# EVK-NORA-W1_SCHEM_0005_Interface_Isolati.net
KiCad netlist of a schematic drawn in Altium Designer
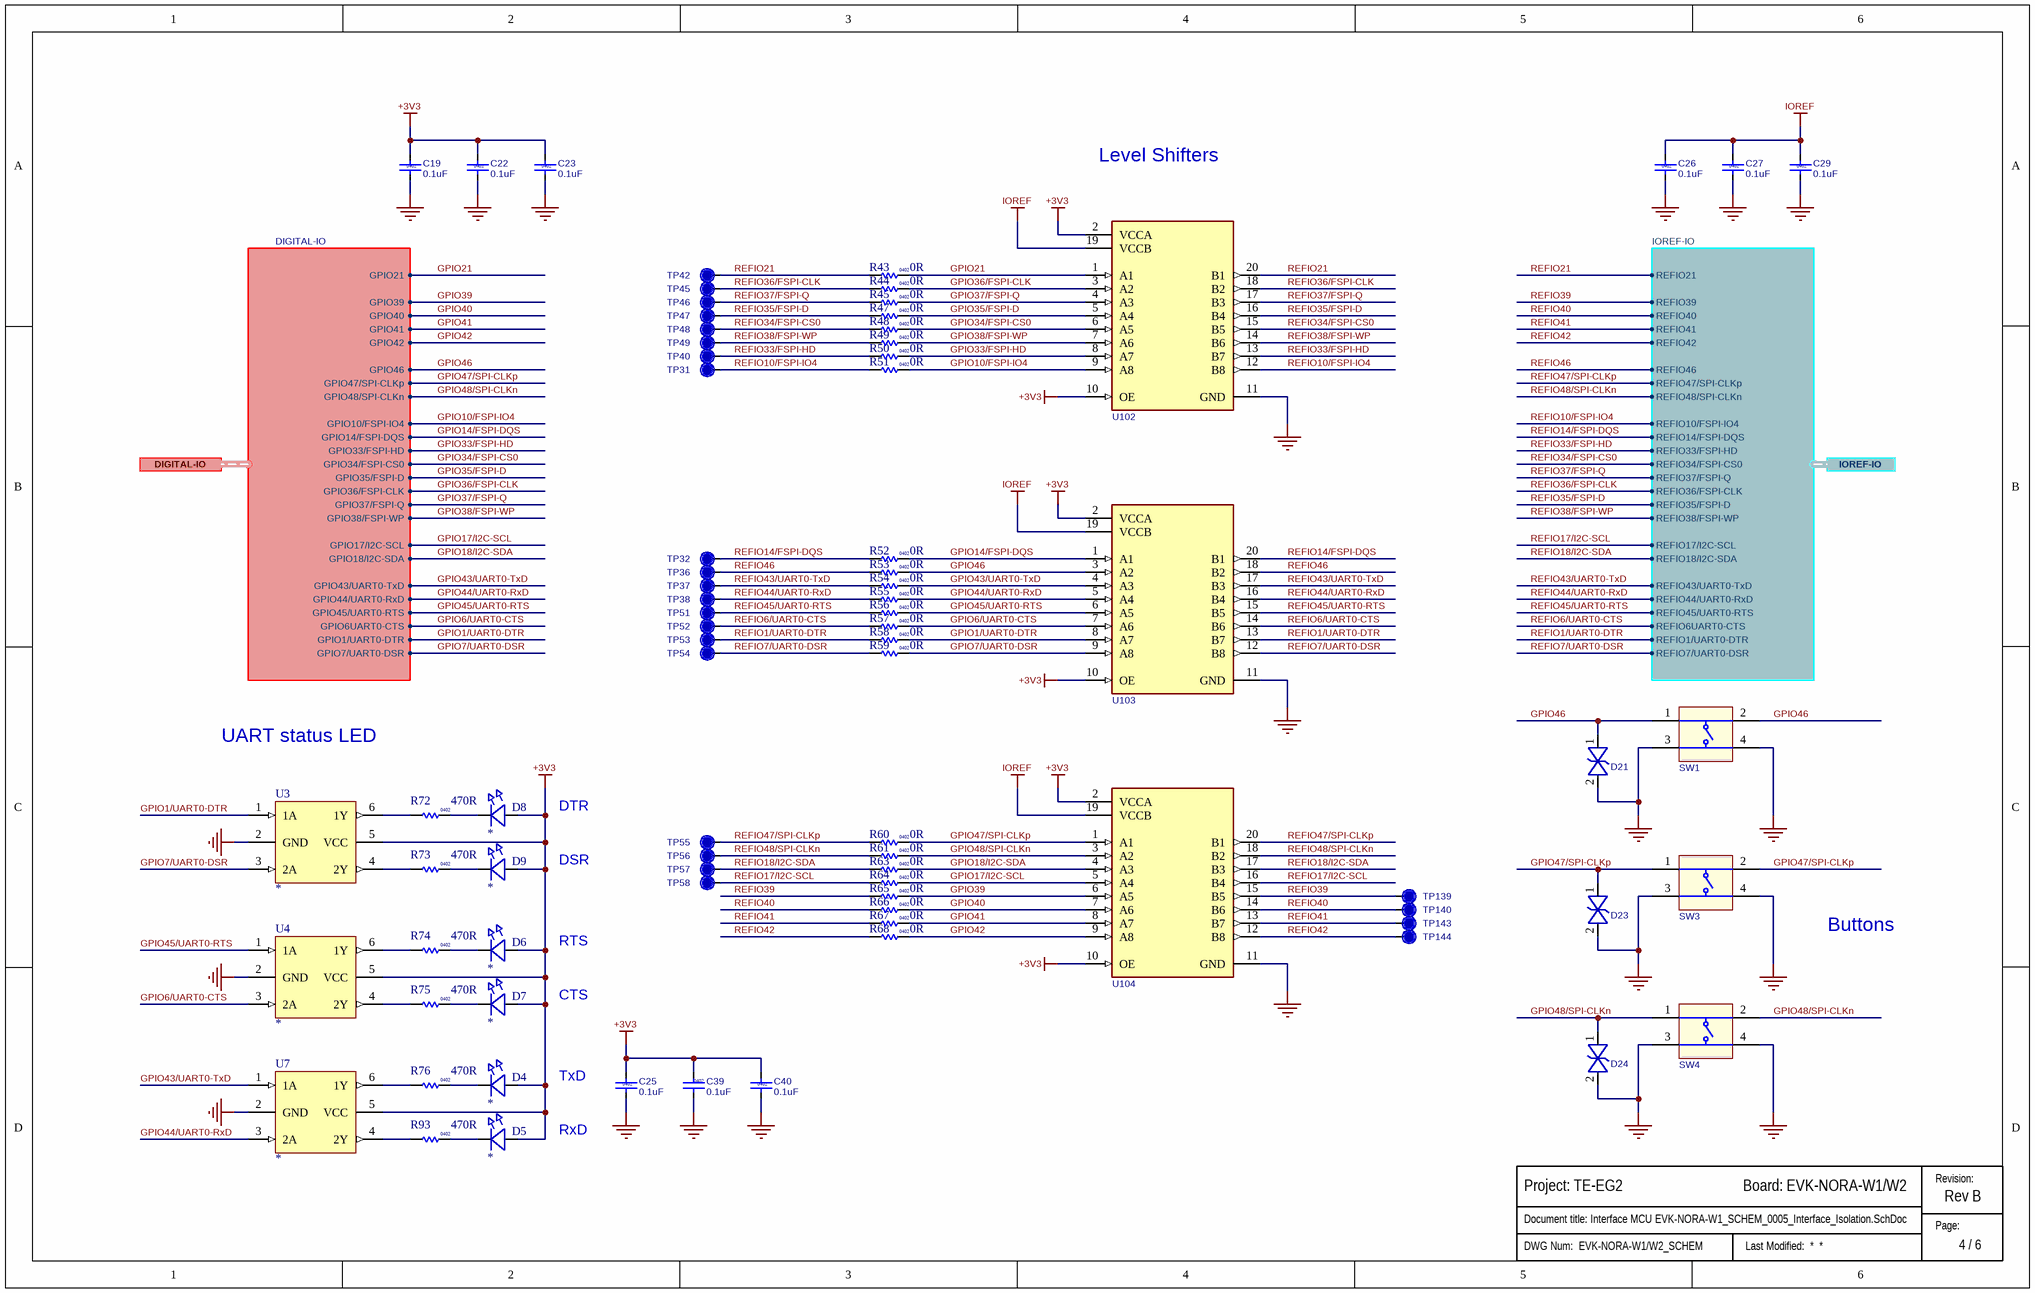
[diagram p0: EVK-NORA-W1_SCHEM_0005_Interface_Isolation.SchDoc]

(export (version "E")
  (design (tool "Eeschema 10.0.6"))
  (components
    (comp (ref "C19")
      (value "0.1uF")
      (footprint "Cap 0402 HD")
      (description "Cap, Ceramic 0.1uF 10V 10% X5R 0402")
      (fields
        (field (name "SIZE") "0402")
        (field (name "PART NUMBER") "120-00016")
        (field (name "MANUFACTURER") "Murata Electronics North America")
      )
      (libsource (lib "Arena_Parts_DB_Lib") (part "Cap Chip"))
    )
    (comp (ref "C22")
      (value "0.1uF")
      (footprint "Cap 0402 HD")
      (description "Cap, Ceramic 0.1uF 10V 10% X5R 0402")
      (fields
        (field (name "SIZE") "0402")
        (field (name "PART NUMBER") "120-00016")
        (field (name "MANUFACTURER") "Murata Electronics North America")
      )
      (libsource (lib "Arena_Parts_DB_Lib") (part "Cap Chip"))
    )
    (comp (ref "C23")
      (value "0.1uF")
      (footprint "Cap 0402 HD")
      (description "Cap, Ceramic 0.1uF 10V 10% X5R 0402")
      (fields
        (field (name "SIZE") "0402")
        (field (name "PART NUMBER") "120-00016")
        (field (name "MANUFACTURER") "Murata Electronics North America")
      )
      (libsource (lib "Arena_Parts_DB_Lib") (part "Cap Chip"))
    )
    (comp (ref "C25")
      (value "0.1uF")
      (footprint "Cap 0402 HD")
      (description "Cap, Ceramic 0.1uF 10V 10% X5R 0402")
      (fields
        (field (name "SIZE") "0402")
        (field (name "PART NUMBER") "120-00016")
        (field (name "MANUFACTURER") "Murata Electronics North America")
      )
      (libsource (lib "Arena_Parts_DB_Lib") (part "Cap Chip"))
    )
    (comp (ref "C26")
      (value "0.1uF")
      (footprint "Cap 0402 HD")
      (description "Cap, Ceramic 0.1uF 10V 10% X5R 0402")
      (fields
        (field (name "SIZE") "0402")
        (field (name "PART NUMBER") "120-00016")
        (field (name "MANUFACTURER") "Murata Electronics North America")
      )
      (libsource (lib "Arena_Parts_DB_Lib") (part "Cap Chip"))
    )
    (comp (ref "C27")
      (value "0.1uF")
      (footprint "Cap 0402 HD")
      (description "Cap, Ceramic 0.1uF 10V 10% X5R 0402")
      (fields
        (field (name "SIZE") "0402")
        (field (name "PART NUMBER") "120-00016")
        (field (name "MANUFACTURER") "Murata Electronics North America")
      )
      (libsource (lib "Arena_Parts_DB_Lib") (part "Cap Chip"))
    )
    (comp (ref "C29")
      (value "0.1uF")
      (footprint "Cap 0402 HD")
      (description "Cap, Ceramic 0.1uF 10V 10% X5R 0402")
      (fields
        (field (name "SIZE") "0402")
        (field (name "PART NUMBER") "120-00016")
        (field (name "MANUFACTURER") "Murata Electronics North America")
      )
      (libsource (lib "Arena_Parts_DB_Lib") (part "Cap Chip"))
    )
    (comp (ref "C39")
      (value "0.1uF")
      (footprint "Cap 0402 HD")
      (description "Cap, Ceramic 0.1uF 10V 10% X5R 0402")
      (fields
        (field (name "SIZE") "0402")
        (field (name "PART NUMBER") "120-00016")
        (field (name "MANUFACTURER") "Murata Electronics North America")
      )
      (libsource (lib "Arena_Parts_DB_Lib") (part "Cap Chip"))
    )
    (comp (ref "C40")
      (value "0.1uF")
      (footprint "Cap 0402 HD")
      (description "Cap, Ceramic 0.1uF 10V 10% X5R 0402")
      (fields
        (field (name "SIZE") "0402")
        (field (name "PART NUMBER") "120-00016")
        (field (name "MANUFACTURER") "Murata Electronics North America")
      )
      (libsource (lib "Arena_Parts_DB_Lib") (part "Cap Chip"))
    )
    (comp (ref "D4")
      (value "UBXH11-0000018")
      (footprint "LED-0603")
      (description "LED CHIP 0603 LOW CURRENT OSRAM 0.002A GREEN 2.2V 2mA")
      (fields
        (field (name "COLOR") "*")
        (field (name "MANUFACTURER") "Osram")
        (field (name "EDITOR") "johann.furrer")
        (field (name "RELEASED BY") "martin.grasse")
      )
      (libsource (lib "UBX_Parts_DB_Lib") (part "LED_BASE"))
    )
    (comp (ref "D5")
      (value "UBXH11-0000018")
      (footprint "LED-0603")
      (description "LED CHIP 0603 LOW CURRENT OSRAM 0.002A GREEN 2.2V 2mA")
      (fields
        (field (name "COLOR") "*")
        (field (name "MANUFACTURER") "Osram")
        (field (name "EDITOR") "johann.furrer")
        (field (name "RELEASED BY") "martin.grasse")
      )
      (libsource (lib "UBX_Parts_DB_Lib") (part "LED_BASE"))
    )
    (comp (ref "D6")
      (value "UBXH11-0000018")
      (footprint "LED-0603")
      (description "LED CHIP 0603 LOW CURRENT OSRAM 0.002A GREEN 2.2V 2mA")
      (fields
        (field (name "COLOR") "*")
        (field (name "MANUFACTURER") "Osram")
        (field (name "EDITOR") "johann.furrer")
        (field (name "RELEASED BY") "martin.grasse")
      )
      (libsource (lib "UBX_Parts_DB_Lib") (part "LED_BASE"))
    )
    (comp (ref "D7")
      (value "UBXH11-0000018")
      (footprint "LED-0603")
      (description "LED CHIP 0603 LOW CURRENT OSRAM 0.002A GREEN 2.2V 2mA")
      (fields
        (field (name "COLOR") "*")
        (field (name "MANUFACTURER") "Osram")
        (field (name "EDITOR") "johann.furrer")
        (field (name "RELEASED BY") "martin.grasse")
      )
      (libsource (lib "UBX_Parts_DB_Lib") (part "LED_BASE"))
    )
    (comp (ref "D8")
      (value "UBXH11-0000018")
      (footprint "LED-0603")
      (description "LED CHIP 0603 LOW CURRENT OSRAM 0.002A GREEN 2.2V 2mA")
      (fields
        (field (name "COLOR") "*")
        (field (name "MANUFACTURER") "Osram")
        (field (name "EDITOR") "johann.furrer")
        (field (name "RELEASED BY") "martin.grasse")
      )
      (libsource (lib "UBX_Parts_DB_Lib") (part "LED_BASE"))
    )
    (comp (ref "D9")
      (value "UBXH11-0000018")
      (footprint "LED-0603")
      (description "LED CHIP 0603 LOW CURRENT OSRAM 0.002A GREEN 2.2V 2mA")
      (fields
        (field (name "COLOR") "*")
        (field (name "MANUFACTURER") "Osram")
        (field (name "EDITOR") "johann.furrer")
        (field (name "RELEASED BY") "martin.grasse")
      )
      (libsource (lib "UBX_Parts_DB_Lib") (part "LED_BASE"))
    )
    (comp (ref "D21")
      (value "110-00019")
      (footprint "SOD-923")
      (description "ESD9B3.3ST5G")
      (fields (field (name "MANUFACTURER") "ON Semiconductor") (field (name "VOLTAGE") "3.3V"))
      (libsource (lib "Arena_Parts_DB_Lib") (part "Diode_TVS"))
    )
    (comp (ref "D23")
      (value "110-00019")
      (footprint "SOD-923")
      (description "ESD9B3.3ST5G")
      (fields (field (name "MANUFACTURER") "ON Semiconductor") (field (name "VOLTAGE") "3.3V"))
      (libsource (lib "Arena_Parts_DB_Lib") (part "Diode_TVS"))
    )
    (comp (ref "D24")
      (value "110-00019")
      (footprint "SOD-923")
      (description "ESD9B3.3ST5G")
      (fields (field (name "MANUFACTURER") "ON Semiconductor") (field (name "VOLTAGE") "3.3V"))
      (libsource (lib "Arena_Parts_DB_Lib") (part "Diode_TVS"))
    )
    (comp (ref "R43")
      (value "0R")
      (footprint "RES 0402 HD")
      (description "RES THICK FILM CHIP 0402 0R 0 100mW")
      (fields
        (field (name "SIZE") "0402")
        (field (name "PART NUMBER") "UBXH18-0003002")
        (field (name "TOLERANCE") "0")
        (field (name "EDITOR") "charlotte.biber")
        (field (name "RELEASED BY") "peter.mueller")
      )
      (libsource (lib "UBX_Parts_DB_Lib") (part "Res sm"))
    )
    (comp (ref "R44")
      (value "0R")
      (footprint "RES 0402 HD")
      (description "RES THICK FILM CHIP 0402 0R 0 100mW")
      (fields
        (field (name "SIZE") "0402")
        (field (name "PART NUMBER") "UBXH18-0003002")
        (field (name "TOLERANCE") "0")
        (field (name "EDITOR") "charlotte.biber")
        (field (name "RELEASED BY") "peter.mueller")
      )
      (libsource (lib "UBX_Parts_DB_Lib") (part "Res sm"))
    )
    (comp (ref "R45")
      (value "0R")
      (footprint "RES 0402 HD")
      (description "RES THICK FILM CHIP 0402 0R 0 100mW")
      (fields
        (field (name "SIZE") "0402")
        (field (name "PART NUMBER") "UBXH18-0003002")
        (field (name "TOLERANCE") "0")
        (field (name "EDITOR") "charlotte.biber")
        (field (name "RELEASED BY") "peter.mueller")
      )
      (libsource (lib "UBX_Parts_DB_Lib") (part "Res sm"))
    )
    (comp (ref "R47")
      (value "0R")
      (footprint "RES 0402 HD")
      (description "RES THICK FILM CHIP 0402 0R 0 100mW")
      (fields
        (field (name "SIZE") "0402")
        (field (name "PART NUMBER") "UBXH18-0003002")
        (field (name "TOLERANCE") "0")
        (field (name "EDITOR") "charlotte.biber")
        (field (name "RELEASED BY") "peter.mueller")
      )
      (libsource (lib "UBX_Parts_DB_Lib") (part "Res sm"))
    )
    (comp (ref "R48")
      (value "0R")
      (footprint "RES 0402 HD")
      (description "RES THICK FILM CHIP 0402 0R 0 100mW")
      (fields
        (field (name "SIZE") "0402")
        (field (name "PART NUMBER") "UBXH18-0003002")
        (field (name "TOLERANCE") "0")
        (field (name "EDITOR") "charlotte.biber")
        (field (name "RELEASED BY") "peter.mueller")
      )
      (libsource (lib "UBX_Parts_DB_Lib") (part "Res sm"))
    )
    (comp (ref "R49")
      (value "0R")
      (footprint "RES 0402 HD")
      (description "RES THICK FILM CHIP 0402 0R 0 100mW")
      (fields
        (field (name "SIZE") "0402")
        (field (name "PART NUMBER") "UBXH18-0003002")
        (field (name "TOLERANCE") "0")
        (field (name "EDITOR") "charlotte.biber")
        (field (name "RELEASED BY") "peter.mueller")
      )
      (libsource (lib "UBX_Parts_DB_Lib") (part "Res sm"))
    )
    (comp (ref "R50")
      (value "0R")
      (footprint "RES 0402 HD")
      (description "RES THICK FILM CHIP 0402 0R 0 100mW")
      (fields
        (field (name "SIZE") "0402")
        (field (name "PART NUMBER") "UBXH18-0003002")
        (field (name "TOLERANCE") "0")
        (field (name "EDITOR") "charlotte.biber")
        (field (name "RELEASED BY") "peter.mueller")
      )
      (libsource (lib "UBX_Parts_DB_Lib") (part "Res sm"))
    )
    (comp (ref "R51")
      (value "0R")
      (footprint "RES 0402 HD")
      (description "RES THICK FILM CHIP 0402 0R 0 100mW")
      (fields
        (field (name "SIZE") "0402")
        (field (name "PART NUMBER") "UBXH18-0003002")
        (field (name "TOLERANCE") "0")
        (field (name "EDITOR") "charlotte.biber")
        (field (name "RELEASED BY") "peter.mueller")
      )
      (libsource (lib "UBX_Parts_DB_Lib") (part "Res sm"))
    )
    (comp (ref "R52")
      (value "0R")
      (footprint "RES 0402 HD")
      (description "RES THICK FILM CHIP 0402 0R 0 100mW")
      (fields
        (field (name "SIZE") "0402")
        (field (name "PART NUMBER") "UBXH18-0003002")
        (field (name "TOLERANCE") "0")
        (field (name "EDITOR") "charlotte.biber")
        (field (name "RELEASED BY") "peter.mueller")
      )
      (libsource (lib "UBX_Parts_DB_Lib") (part "Res sm"))
    )
    (comp (ref "R53")
      (value "0R")
      (footprint "RES 0402 HD")
      (description "RES THICK FILM CHIP 0402 0R 0 100mW")
      (fields
        (field (name "SIZE") "0402")
        (field (name "PART NUMBER") "UBXH18-0003002")
        (field (name "TOLERANCE") "0")
        (field (name "EDITOR") "charlotte.biber")
        (field (name "RELEASED BY") "peter.mueller")
      )
      (libsource (lib "UBX_Parts_DB_Lib") (part "Res sm"))
    )
    (comp (ref "R54")
      (value "0R")
      (footprint "RES 0402 HD")
      (description "RES THICK FILM CHIP 0402 0R 0 100mW")
      (fields
        (field (name "SIZE") "0402")
        (field (name "PART NUMBER") "UBXH18-0003002")
        (field (name "TOLERANCE") "0")
        (field (name "EDITOR") "charlotte.biber")
        (field (name "RELEASED BY") "peter.mueller")
      )
      (libsource (lib "UBX_Parts_DB_Lib") (part "Res sm"))
    )
    (comp (ref "R55")
      (value "0R")
      (footprint "RES 0402 HD")
      (description "RES THICK FILM CHIP 0402 0R 0 100mW")
      (fields
        (field (name "SIZE") "0402")
        (field (name "PART NUMBER") "UBXH18-0003002")
        (field (name "TOLERANCE") "0")
        (field (name "EDITOR") "charlotte.biber")
        (field (name "RELEASED BY") "peter.mueller")
      )
      (libsource (lib "UBX_Parts_DB_Lib") (part "Res sm"))
    )
    (comp (ref "R56")
      (value "0R")
      (footprint "RES 0402 HD")
      (description "RES THICK FILM CHIP 0402 0R 0 100mW")
      (fields
        (field (name "SIZE") "0402")
        (field (name "PART NUMBER") "UBXH18-0003002")
        (field (name "TOLERANCE") "0")
        (field (name "EDITOR") "charlotte.biber")
        (field (name "RELEASED BY") "peter.mueller")
      )
      (libsource (lib "UBX_Parts_DB_Lib") (part "Res sm"))
    )
    (comp (ref "R57")
      (value "0R")
      (footprint "RES 0402 HD")
      (description "RES THICK FILM CHIP 0402 0R 0 100mW")
      (fields
        (field (name "SIZE") "0402")
        (field (name "PART NUMBER") "UBXH18-0003002")
        (field (name "TOLERANCE") "0")
        (field (name "EDITOR") "charlotte.biber")
        (field (name "RELEASED BY") "peter.mueller")
      )
      (libsource (lib "UBX_Parts_DB_Lib") (part "Res sm"))
    )
    (comp (ref "R58")
      (value "0R")
      (footprint "RES 0402 HD")
      (description "RES THICK FILM CHIP 0402 0R 0 100mW")
      (fields
        (field (name "SIZE") "0402")
        (field (name "PART NUMBER") "UBXH18-0003002")
        (field (name "TOLERANCE") "0")
        (field (name "EDITOR") "charlotte.biber")
        (field (name "RELEASED BY") "peter.mueller")
      )
      (libsource (lib "UBX_Parts_DB_Lib") (part "Res sm"))
    )
    (comp (ref "R59")
      (value "0R")
      (footprint "RES 0402 HD")
      (description "RES THICK FILM CHIP 0402 0R 0 100mW")
      (fields
        (field (name "SIZE") "0402")
        (field (name "PART NUMBER") "UBXH18-0003002")
        (field (name "TOLERANCE") "0")
        (field (name "EDITOR") "charlotte.biber")
        (field (name "RELEASED BY") "peter.mueller")
      )
      (libsource (lib "UBX_Parts_DB_Lib") (part "Res sm"))
    )
    (comp (ref "R60")
      (value "0R")
      (footprint "RES 0402 HD")
      (description "RES THICK FILM CHIP 0402 0R 0 100mW")
      (fields
        (field (name "SIZE") "0402")
        (field (name "PART NUMBER") "UBXH18-0003002")
        (field (name "TOLERANCE") "0")
        (field (name "EDITOR") "charlotte.biber")
        (field (name "RELEASED BY") "peter.mueller")
      )
      (libsource (lib "UBX_Parts_DB_Lib") (part "Res sm"))
    )
    (comp (ref "R61")
      (value "0R")
      (footprint "RES 0402 HD")
      (description "RES THICK FILM CHIP 0402 0R 0 100mW")
      (fields
        (field (name "SIZE") "0402")
        (field (name "PART NUMBER") "UBXH18-0003002")
        (field (name "TOLERANCE") "0")
        (field (name "EDITOR") "charlotte.biber")
        (field (name "RELEASED BY") "peter.mueller")
      )
      (libsource (lib "UBX_Parts_DB_Lib") (part "Res sm"))
    )
    (comp (ref "R63")
      (value "0R")
      (footprint "RES 0402 HD")
      (description "RES THICK FILM CHIP 0402 0R 0 100mW")
      (fields
        (field (name "SIZE") "0402")
        (field (name "PART NUMBER") "UBXH18-0003002")
        (field (name "TOLERANCE") "0")
        (field (name "EDITOR") "charlotte.biber")
        (field (name "RELEASED BY") "peter.mueller")
      )
      (libsource (lib "UBX_Parts_DB_Lib") (part "Res sm"))
    )
    (comp (ref "R64")
      (value "0R")
      (footprint "RES 0402 HD")
      (description "RES THICK FILM CHIP 0402 0R 0 100mW")
      (fields
        (field (name "SIZE") "0402")
        (field (name "PART NUMBER") "UBXH18-0003002")
        (field (name "TOLERANCE") "0")
        (field (name "EDITOR") "charlotte.biber")
        (field (name "RELEASED BY") "peter.mueller")
      )
      (libsource (lib "UBX_Parts_DB_Lib") (part "Res sm"))
    )
    (comp (ref "R65")
      (value "0R")
      (footprint "RES 0402 HD")
      (description "RES THICK FILM CHIP 0402 0R 0 100mW")
      (fields
        (field (name "SIZE") "0402")
        (field (name "PART NUMBER") "UBXH18-0003002")
        (field (name "TOLERANCE") "0")
        (field (name "EDITOR") "charlotte.biber")
        (field (name "RELEASED BY") "peter.mueller")
      )
      (libsource (lib "UBX_Parts_DB_Lib") (part "Res sm"))
    )
    (comp (ref "R66")
      (value "0R")
      (footprint "RES 0402 HD")
      (description "RES THICK FILM CHIP 0402 0R 0 100mW")
      (fields
        (field (name "SIZE") "0402")
        (field (name "PART NUMBER") "UBXH18-0003002")
        (field (name "TOLERANCE") "0")
        (field (name "EDITOR") "charlotte.biber")
        (field (name "RELEASED BY") "peter.mueller")
      )
      (libsource (lib "UBX_Parts_DB_Lib") (part "Res sm"))
    )
    (comp (ref "R67")
      (value "0R")
      (footprint "RES 0402 HD")
      (description "RES THICK FILM CHIP 0402 0R 0 100mW")
      (fields
        (field (name "SIZE") "0402")
        (field (name "PART NUMBER") "UBXH18-0003002")
        (field (name "TOLERANCE") "0")
        (field (name "EDITOR") "charlotte.biber")
        (field (name "RELEASED BY") "peter.mueller")
      )
      (libsource (lib "UBX_Parts_DB_Lib") (part "Res sm"))
    )
    (comp (ref "R68")
      (value "0R")
      (footprint "RES 0402 HD")
      (description "RES THICK FILM CHIP 0402 0R 0 100mW")
      (fields
        (field (name "SIZE") "0402")
        (field (name "PART NUMBER") "UBXH18-0003002")
        (field (name "TOLERANCE") "0")
        (field (name "EDITOR") "charlotte.biber")
        (field (name "RELEASED BY") "peter.mueller")
      )
      (libsource (lib "UBX_Parts_DB_Lib") (part "Res sm"))
    )
    (comp (ref "R72")
      (value "470R")
      (footprint "RES 0402 HD")
      (description "RES THICK FILM CHIP 0402 470R 5% 100mW")
      (fields
        (field (name "SIZE") "0402")
        (field (name "PART NUMBER") "UBXH18-0008041")
        (field (name "TOLERANCE") "5%")
        (field (name "EDITOR") "roland.rust")
        (field (name "RELEASED BY") "roland.rust")
      )
      (libsource (lib "UBX_Parts_DB_Lib") (part "Res sm"))
    )
    (comp (ref "R73")
      (value "470R")
      (footprint "RES 0402 HD")
      (description "RES THICK FILM CHIP 0402 470R 5% 100mW")
      (fields
        (field (name "SIZE") "0402")
        (field (name "PART NUMBER") "UBXH18-0008041")
        (field (name "TOLERANCE") "5%")
        (field (name "EDITOR") "roland.rust")
        (field (name "RELEASED BY") "roland.rust")
      )
      (libsource (lib "UBX_Parts_DB_Lib") (part "Res sm"))
    )
    (comp (ref "R74")
      (value "470R")
      (footprint "RES 0402 HD")
      (description "RES THICK FILM CHIP 0402 470R 5% 100mW")
      (fields
        (field (name "SIZE") "0402")
        (field (name "PART NUMBER") "UBXH18-0008041")
        (field (name "TOLERANCE") "5%")
        (field (name "EDITOR") "roland.rust")
        (field (name "RELEASED BY") "roland.rust")
      )
      (libsource (lib "UBX_Parts_DB_Lib") (part "Res sm"))
    )
    (comp (ref "R75")
      (value "470R")
      (footprint "RES 0402 HD")
      (description "RES THICK FILM CHIP 0402 470R 5% 100mW")
      (fields
        (field (name "SIZE") "0402")
        (field (name "PART NUMBER") "UBXH18-0008041")
        (field (name "TOLERANCE") "5%")
        (field (name "EDITOR") "roland.rust")
        (field (name "RELEASED BY") "roland.rust")
      )
      (libsource (lib "UBX_Parts_DB_Lib") (part "Res sm"))
    )
    (comp (ref "R76")
      (value "470R")
      (footprint "RES 0402 HD")
      (description "RES THICK FILM CHIP 0402 470R 5% 100mW")
      (fields
        (field (name "SIZE") "0402")
        (field (name "PART NUMBER") "UBXH18-0008041")
        (field (name "TOLERANCE") "5%")
        (field (name "EDITOR") "roland.rust")
        (field (name "RELEASED BY") "roland.rust")
      )
      (libsource (lib "UBX_Parts_DB_Lib") (part "Res sm"))
    )
    (comp (ref "R93")
      (value "470R")
      (footprint "RES 0402 HD")
      (description "RES THICK FILM CHIP 0402 470R 5% 100mW")
      (fields
        (field (name "SIZE") "0402")
        (field (name "PART NUMBER") "UBXH18-0008041")
        (field (name "TOLERANCE") "5%")
        (field (name "EDITOR") "roland.rust")
        (field (name "RELEASED BY") "roland.rust")
      )
      (libsource (lib "UBX_Parts_DB_Lib") (part "Res sm"))
    )
    (comp (ref "SW1")
      (value "135-00002")
      (footprint "SW_TACT_SMT_6mm")
      (description "Tactile Switch, SPST-NO, SMT, Actuation force = 160g, 6mm x 6mm")
      (fields (field (name "MANUFACTURER") "C&K Components") (field (name "VOLTAGE") "12VDC"))
      (libsource (lib "Arena_Parts_DB_Lib") (part "SW_TACT_SPST_4Pin"))
    )
    (comp (ref "SW3")
      (value "135-00002")
      (footprint "SW_TACT_SMT_6mm")
      (description "Tactile Switch, SPST-NO, SMT, Actuation force = 160g, 6mm x 6mm")
      (fields (field (name "MANUFACTURER") "C&K Components") (field (name "VOLTAGE") "12VDC"))
      (libsource (lib "Arena_Parts_DB_Lib") (part "SW_TACT_SPST_4Pin"))
    )
    (comp (ref "SW4")
      (value "135-00002")
      (footprint "SW_TACT_SMT_6mm")
      (description "Tactile Switch, SPST-NO, SMT, Actuation force = 160g, 6mm x 6mm")
      (fields (field (name "MANUFACTURER") "C&K Components") (field (name "VOLTAGE") "12VDC"))
      (libsource (lib "Arena_Parts_DB_Lib") (part "SW_TACT_SPST_4Pin"))
    )
    (comp (ref "TP31")
      (value "TP")
      (footprint "TP10R")
      (description "Testpoint, Round 1.0mm Dia")
      (fields
        (field (name "PART NUMBER") "TP10R")
        (field (name "ADDED BY") "Jeremy D")
        (field (name "CHECKED BY") "Paul B")
      )
      (libsource (lib "LEGACY_Rigado_AltiumLib") (part "TP_R"))
    )
    (comp (ref "TP32")
      (value "TP")
      (footprint "TP10R")
      (description "Testpoint, Round 1.0mm Dia")
      (fields
        (field (name "PART NUMBER") "TP10R")
        (field (name "ADDED BY") "Jeremy D")
        (field (name "CHECKED BY") "Paul B")
      )
      (libsource (lib "LEGACY_Rigado_AltiumLib") (part "TP_R"))
    )
    (comp (ref "TP36")
      (value "TP")
      (footprint "TP10R")
      (description "Testpoint, Round 1.0mm Dia")
      (fields
        (field (name "PART NUMBER") "TP10R")
        (field (name "ADDED BY") "Jeremy D")
        (field (name "CHECKED BY") "Paul B")
      )
      (libsource (lib "LEGACY_Rigado_AltiumLib") (part "TP_R"))
    )
    (comp (ref "TP37")
      (value "TP")
      (footprint "TP10R")
      (description "Testpoint, Round 1.0mm Dia")
      (fields
        (field (name "PART NUMBER") "TP10R")
        (field (name "ADDED BY") "Jeremy D")
        (field (name "CHECKED BY") "Paul B")
      )
      (libsource (lib "LEGACY_Rigado_AltiumLib") (part "TP_R"))
    )
    (comp (ref "TP38")
      (value "TP")
      (footprint "TP10R")
      (description "Testpoint, Round 1.0mm Dia")
      (fields
        (field (name "PART NUMBER") "TP10R")
        (field (name "ADDED BY") "Jeremy D")
        (field (name "CHECKED BY") "Paul B")
      )
      (libsource (lib "LEGACY_Rigado_AltiumLib") (part "TP_R"))
    )
    (comp (ref "TP40")
      (value "TP")
      (footprint "TP10R")
      (description "Testpoint, Round 1.0mm Dia")
      (fields
        (field (name "PART NUMBER") "TP10R")
        (field (name "ADDED BY") "Jeremy D")
        (field (name "CHECKED BY") "Paul B")
      )
      (libsource (lib "LEGACY_Rigado_AltiumLib") (part "TP_R"))
    )
    (comp (ref "TP42")
      (value "TP")
      (footprint "TP10R")
      (description "Testpoint, Round 1.0mm Dia")
      (fields
        (field (name "PART NUMBER") "TP10R")
        (field (name "ADDED BY") "Jeremy D")
        (field (name "CHECKED BY") "Paul B")
      )
      (libsource (lib "LEGACY_Rigado_AltiumLib") (part "TP_R"))
    )
    (comp (ref "TP45")
      (value "TP")
      (footprint "TP10R")
      (description "Testpoint, Round 1.0mm Dia")
      (fields
        (field (name "PART NUMBER") "TP10R")
        (field (name "ADDED BY") "Jeremy D")
        (field (name "CHECKED BY") "Paul B")
      )
      (libsource (lib "LEGACY_Rigado_AltiumLib") (part "TP_R"))
    )
    (comp (ref "TP46")
      (value "TP")
      (footprint "TP10R")
      (description "Testpoint, Round 1.0mm Dia")
      (fields
        (field (name "PART NUMBER") "TP10R")
        (field (name "ADDED BY") "Jeremy D")
        (field (name "CHECKED BY") "Paul B")
      )
      (libsource (lib "LEGACY_Rigado_AltiumLib") (part "TP_R"))
    )
    (comp (ref "TP47")
      (value "TP")
      (footprint "TP10R")
      (description "Testpoint, Round 1.0mm Dia")
      (fields
        (field (name "PART NUMBER") "TP10R")
        (field (name "ADDED BY") "Jeremy D")
        (field (name "CHECKED BY") "Paul B")
      )
      (libsource (lib "LEGACY_Rigado_AltiumLib") (part "TP_R"))
    )
    (comp (ref "TP48")
      (value "TP")
      (footprint "TP10R")
      (description "Testpoint, Round 1.0mm Dia")
      (fields
        (field (name "PART NUMBER") "TP10R")
        (field (name "ADDED BY") "Jeremy D")
        (field (name "CHECKED BY") "Paul B")
      )
      (libsource (lib "LEGACY_Rigado_AltiumLib") (part "TP_R"))
    )
    (comp (ref "TP49")
      (value "TP")
      (footprint "TP10R")
      (description "Testpoint, Round 1.0mm Dia")
      (fields
        (field (name "PART NUMBER") "TP10R")
        (field (name "ADDED BY") "Jeremy D")
        (field (name "CHECKED BY") "Paul B")
      )
      (libsource (lib "LEGACY_Rigado_AltiumLib") (part "TP_R"))
    )
    (comp (ref "TP51")
      (value "TP")
      (footprint "TP10R")
      (description "Testpoint, Round 1.0mm Dia")
      (fields
        (field (name "PART NUMBER") "TP10R")
        (field (name "ADDED BY") "Jeremy D")
        (field (name "CHECKED BY") "Paul B")
      )
      (libsource (lib "LEGACY_Rigado_AltiumLib") (part "TP_R"))
    )
    (comp (ref "TP52")
      (value "TP")
      (footprint "TP10R")
      (description "Testpoint, Round 1.0mm Dia")
      (fields
        (field (name "PART NUMBER") "TP10R")
        (field (name "ADDED BY") "Jeremy D")
        (field (name "CHECKED BY") "Paul B")
      )
      (libsource (lib "LEGACY_Rigado_AltiumLib") (part "TP_R"))
    )
    (comp (ref "TP53")
      (value "TP")
      (footprint "TP10R")
      (description "Testpoint, Round 1.0mm Dia")
      (fields
        (field (name "PART NUMBER") "TP10R")
        (field (name "ADDED BY") "Jeremy D")
        (field (name "CHECKED BY") "Paul B")
      )
      (libsource (lib "LEGACY_Rigado_AltiumLib") (part "TP_R"))
    )
    (comp (ref "TP54")
      (value "TP")
      (footprint "TP10R")
      (description "Testpoint, Round 1.0mm Dia")
      (fields
        (field (name "PART NUMBER") "TP10R")
        (field (name "ADDED BY") "Jeremy D")
        (field (name "CHECKED BY") "Paul B")
      )
      (libsource (lib "LEGACY_Rigado_AltiumLib") (part "TP_R"))
    )
    (comp (ref "TP55")
      (value "TP")
      (footprint "TP10R")
      (description "Testpoint, Round 1.0mm Dia")
      (fields
        (field (name "PART NUMBER") "TP10R")
        (field (name "ADDED BY") "Jeremy D")
        (field (name "CHECKED BY") "Paul B")
      )
      (libsource (lib "LEGACY_Rigado_AltiumLib") (part "TP_R"))
    )
    (comp (ref "TP56")
      (value "TP")
      (footprint "TP10R")
      (description "Testpoint, Round 1.0mm Dia")
      (fields
        (field (name "PART NUMBER") "TP10R")
        (field (name "ADDED BY") "Jeremy D")
        (field (name "CHECKED BY") "Paul B")
      )
      (libsource (lib "LEGACY_Rigado_AltiumLib") (part "TP_R"))
    )
    (comp (ref "TP57")
      (value "TP")
      (footprint "TP10R")
      (description "Testpoint, Round 1.0mm Dia")
      (fields
        (field (name "PART NUMBER") "TP10R")
        (field (name "ADDED BY") "Jeremy D")
        (field (name "CHECKED BY") "Paul B")
      )
      (libsource (lib "LEGACY_Rigado_AltiumLib") (part "TP_R"))
    )
    (comp (ref "TP58")
      (value "TP")
      (footprint "TP10R")
      (description "Testpoint, Round 1.0mm Dia")
      (fields
        (field (name "PART NUMBER") "TP10R")
        (field (name "ADDED BY") "Jeremy D")
        (field (name "CHECKED BY") "Paul B")
      )
      (libsource (lib "LEGACY_Rigado_AltiumLib") (part "TP_R"))
    )
    (comp (ref "TP139")
      (value "TP")
      (footprint "TP10R")
      (description "Testpoint, Round 1.0mm Dia")
      (fields
        (field (name "PART NUMBER") "TP10R")
        (field (name "ADDED BY") "Jeremy D")
        (field (name "CHECKED BY") "Paul B")
      )
      (libsource (lib "LEGACY_Rigado_AltiumLib") (part "TP_R"))
    )
    (comp (ref "TP140")
      (value "TP")
      (footprint "TP10R")
      (description "Testpoint, Round 1.0mm Dia")
      (fields
        (field (name "PART NUMBER") "TP10R")
        (field (name "ADDED BY") "Jeremy D")
        (field (name "CHECKED BY") "Paul B")
      )
      (libsource (lib "LEGACY_Rigado_AltiumLib") (part "TP_R"))
    )
    (comp (ref "TP143")
      (value "TP")
      (footprint "TP10R")
      (description "Testpoint, Round 1.0mm Dia")
      (fields
        (field (name "PART NUMBER") "TP10R")
        (field (name "ADDED BY") "Jeremy D")
        (field (name "CHECKED BY") "Paul B")
      )
      (libsource (lib "LEGACY_Rigado_AltiumLib") (part "TP_R"))
    )
    (comp (ref "TP144")
      (value "TP")
      (footprint "TP10R")
      (description "Testpoint, Round 1.0mm Dia")
      (fields
        (field (name "PART NUMBER") "TP10R")
        (field (name "ADDED BY") "Jeremy D")
        (field (name "CHECKED BY") "Paul B")
      )
      (libsource (lib "LEGACY_Rigado_AltiumLib") (part "TP_R"))
    )
    (comp (ref "U3")
      (value "225-00022")
      (footprint "SC70-6")
      (description "Buffer, Non-Inverting 2 Element 1 Bit per Element Push-Pull Output SC-70-6")
      (fields (field (name "MANUFACTURER P/N") "*") (field (name "VOLTAGE") "5.5V"))
      (libsource (lib "Arena_Parts_DB_Lib") (part "Buffer_2bit"))
    )
    (comp (ref "U4")
      (value "225-00022")
      (footprint "SC70-6")
      (description "Buffer, Non-Inverting 2 Element 1 Bit per Element Push-Pull Output SC-70-6")
      (fields (field (name "MANUFACTURER P/N") "*") (field (name "VOLTAGE") "5.5V"))
      (libsource (lib "Arena_Parts_DB_Lib") (part "Buffer_2bit"))
    )
    (comp (ref "U7")
      (value "225-00022")
      (footprint "SC70-6")
      (description "Buffer, Non-Inverting 2 Element 1 Bit per Element Push-Pull Output SC-70-6")
      (fields (field (name "MANUFACTURER P/N") "*") (field (name "VOLTAGE") "5.5V"))
      (libsource (lib "Arena_Parts_DB_Lib") (part "Buffer_2bit"))
    )
    (comp (ref "U102")
      (value "TXS0108EPWR")
      (footprint "TSSOP-20Pin-6.5x6.4")
      (description "TXS0108 8-BIT BIDIRECTIONAL VOLTAGE-LEVEL TRANSLATOR")
      (fields
        (field (name "PART NUMBER") "UBXH10-0000036")
        (field (name "MANUFACTURER") "Texas Instruments")
        (field (name "EDITOR") "roland.rust")
        (field (name "RELEASED BY") "adam.johansson")
      )
      (libsource (lib "UBX_Parts_DB_Lib") (part "TXS0108EPWR"))
    )
    (comp (ref "U103")
      (value "TXS0108EPWR")
      (footprint "TSSOP-20Pin-6.5x6.4")
      (description "TXS0108 8-BIT BIDIRECTIONAL VOLTAGE-LEVEL TRANSLATOR")
      (fields
        (field (name "PART NUMBER") "UBXH10-0000036")
        (field (name "MANUFACTURER") "Texas Instruments")
        (field (name "EDITOR") "roland.rust")
        (field (name "RELEASED BY") "adam.johansson")
      )
      (libsource (lib "UBX_Parts_DB_Lib") (part "TXS0108EPWR"))
    )
    (comp (ref "U104")
      (value "TXS0108EPWR")
      (footprint "TSSOP-20Pin-6.5x6.4")
      (description "TXS0108 8-BIT BIDIRECTIONAL VOLTAGE-LEVEL TRANSLATOR")
      (fields
        (field (name "PART NUMBER") "UBXH10-0000036")
        (field (name "MANUFACTURER") "Texas Instruments")
        (field (name "EDITOR") "roland.rust")
        (field (name "RELEASED BY") "adam.johansson")
      )
      (libsource (lib "UBX_Parts_DB_Lib") (part "TXS0108EPWR"))
    )
  )
  (nets
    (net (code "3") (name "+3V3") (class "Default")
      (node (ref "C19") (pin "1") (pinfunction "1_1") (pintype "passive"))
      (node (ref "C22") (pin "1") (pinfunction "1_1") (pintype "passive"))
      (node (ref "C23") (pin "1") (pinfunction "1_1") (pintype "passive"))
      (node (ref "C25") (pin "1") (pinfunction "1_1") (pintype "passive"))
      (node (ref "C39") (pin "1") (pinfunction "1_1") (pintype "passive"))
      (node (ref "C40") (pin "1") (pinfunction "1_1") (pintype "passive"))
      (node (ref "D4") (pin "2") (pinfunction "A_2") (pintype "passive"))
      (node (ref "D5") (pin "2") (pinfunction "A_2") (pintype "passive"))
      (node (ref "D6") (pin "2") (pinfunction "A_2") (pintype "passive"))
      (node (ref "D7") (pin "2") (pinfunction "A_2") (pintype "passive"))
      (node (ref "D8") (pin "2") (pinfunction "A_2") (pintype "passive"))
      (node (ref "D9") (pin "2") (pinfunction "A_2") (pintype "passive"))
      (node (ref "U102") (pin "10") (pinfunction "OE_10") (pintype "input"))
      (node (ref "U102") (pin "2") (pinfunction "VCCA_2") (pintype "power_in"))
      (node (ref "U103") (pin "10") (pinfunction "OE_10") (pintype "input"))
      (node (ref "U103") (pin "2") (pinfunction "VCCA_2") (pintype "power_in"))
      (node (ref "U104") (pin "10") (pinfunction "OE_10") (pintype "input"))
      (node (ref "U104") (pin "2") (pinfunction "VCCA_2") (pintype "power_in"))
      (node (ref "U3") (pin "5") (pinfunction "VCC_5") (pintype "power_in"))
      (node (ref "U4") (pin "5") (pinfunction "VCC_5") (pintype "power_in"))
      (node (ref "U7") (pin "5") (pinfunction "VCC_5") (pintype "power_in"))
    )
    (net (code "4") (name "/GPIO1{slash}UART0-DTR") (class "Default")
      (node (ref "R58") (pin "2") (pinfunction "2_2") (pintype "passive"))
      (node (ref "U103") (pin "8") (pinfunction "A7_8") (pintype "input"))
      (node (ref "U3") (pin "1") (pinfunction "1A_1") (pintype "input"))
    )
    (net (code "5") (name "/GPIO6{slash}UART0-CTS") (class "Default")
      (node (ref "R57") (pin "2") (pinfunction "2_2") (pintype "passive"))
      (node (ref "U103") (pin "7") (pinfunction "A6_7") (pintype "input"))
      (node (ref "U4") (pin "3") (pinfunction "2A_3") (pintype "input"))
    )
    (net (code "6") (name "/GPIO7{slash}UART0-DSR") (class "Default")
      (node (ref "R59") (pin "2") (pinfunction "2_2") (pintype "passive"))
      (node (ref "U103") (pin "9") (pinfunction "A8_9") (pintype "input"))
      (node (ref "U3") (pin "3") (pinfunction "2A_3") (pintype "input"))
    )
    (net (code "7") (name "/GPIO10{slash}FSPI-IO4") (class "Default")
      (node (ref "R51") (pin "2") (pinfunction "2_2") (pintype "passive"))
      (node (ref "U102") (pin "9") (pinfunction "A8_9") (pintype "input"))
    )
    (net (code "8") (name "/GPIO14{slash}FSPI-DQS") (class "Default")
      (node (ref "R52") (pin "2") (pinfunction "2_2") (pintype "passive"))
      (node (ref "U103") (pin "1") (pinfunction "A1_1") (pintype "input"))
    )
    (net (code "9") (name "/GPIO17{slash}I2C-SCL") (class "Default")
      (node (ref "R64") (pin "2") (pinfunction "2_2") (pintype "passive"))
      (node (ref "U104") (pin "5") (pinfunction "A4_5") (pintype "input"))
    )
    (net (code "10") (name "/GPIO18{slash}I2C-SDA") (class "Default")
      (node (ref "R63") (pin "2") (pinfunction "2_2") (pintype "passive"))
      (node (ref "U104") (pin "4") (pinfunction "A3_4") (pintype "input"))
    )
    (net (code "11") (name "/GPIO21") (class "Default")
      (node (ref "R43") (pin "2") (pinfunction "2_2") (pintype "passive"))
      (node (ref "U102") (pin "1") (pinfunction "A1_1") (pintype "input"))
    )
    (net (code "12") (name "/GPIO33{slash}FSPI-HD") (class "Default")
      (node (ref "R50") (pin "2") (pinfunction "2_2") (pintype "passive"))
      (node (ref "U102") (pin "8") (pinfunction "A7_8") (pintype "input"))
    )
    (net (code "13") (name "/GPIO34{slash}FSPI-CS0") (class "Default")
      (node (ref "R48") (pin "2") (pinfunction "2_2") (pintype "passive"))
      (node (ref "U102") (pin "6") (pinfunction "A5_6") (pintype "input"))
    )
    (net (code "14") (name "/GPIO35{slash}FSPI-D") (class "Default")
      (node (ref "R47") (pin "2") (pinfunction "2_2") (pintype "passive"))
      (node (ref "U102") (pin "5") (pinfunction "A4_5") (pintype "input"))
    )
    (net (code "15") (name "/GPIO36{slash}FSPI-CLK") (class "Default")
      (node (ref "R44") (pin "2") (pinfunction "2_2") (pintype "passive"))
      (node (ref "U102") (pin "3") (pinfunction "A2_3") (pintype "input"))
    )
    (net (code "16") (name "/GPIO37{slash}FSPI-Q") (class "Default")
      (node (ref "R45") (pin "2") (pinfunction "2_2") (pintype "passive"))
      (node (ref "U102") (pin "4") (pinfunction "A3_4") (pintype "input"))
    )
    (net (code "17") (name "/GPIO38{slash}FSPI-WP") (class "Default")
      (node (ref "R49") (pin "2") (pinfunction "2_2") (pintype "passive"))
      (node (ref "U102") (pin "7") (pinfunction "A6_7") (pintype "input"))
    )
    (net (code "18") (name "/GPIO39") (class "Default")
      (node (ref "R65") (pin "2") (pinfunction "2_2") (pintype "passive"))
      (node (ref "U104") (pin "6") (pinfunction "A5_6") (pintype "input"))
    )
    (net (code "19") (name "/GPIO40") (class "Default")
      (node (ref "R66") (pin "2") (pinfunction "2_2") (pintype "passive"))
      (node (ref "U104") (pin "7") (pinfunction "A6_7") (pintype "input"))
    )
    (net (code "20") (name "/GPIO41") (class "Default")
      (node (ref "R67") (pin "2") (pinfunction "2_2") (pintype "passive"))
      (node (ref "U104") (pin "8") (pinfunction "A7_8") (pintype "input"))
    )
    (net (code "21") (name "/GPIO42") (class "Default")
      (node (ref "R68") (pin "2") (pinfunction "2_2") (pintype "passive"))
      (node (ref "U104") (pin "9") (pinfunction "A8_9") (pintype "input"))
    )
    (net (code "22") (name "/GPIO43{slash}UART0-TxD") (class "Default")
      (node (ref "R54") (pin "2") (pinfunction "2_2") (pintype "passive"))
      (node (ref "U103") (pin "4") (pinfunction "A3_4") (pintype "input"))
      (node (ref "U7") (pin "1") (pinfunction "1A_1") (pintype "input"))
    )
    (net (code "23") (name "/GPIO44{slash}UART0-RxD") (class "Default")
      (node (ref "R55") (pin "2") (pinfunction "2_2") (pintype "passive"))
      (node (ref "U103") (pin "5") (pinfunction "A4_5") (pintype "input"))
      (node (ref "U7") (pin "3") (pinfunction "2A_3") (pintype "input"))
    )
    (net (code "24") (name "/GPIO45{slash}UART0-RTS") (class "Default")
      (node (ref "R56") (pin "2") (pinfunction "2_2") (pintype "passive"))
      (node (ref "U103") (pin "6") (pinfunction "A5_6") (pintype "input"))
      (node (ref "U4") (pin "1") (pinfunction "1A_1") (pintype "input"))
    )
    (net (code "25") (name "/GPIO46") (class "Default")
      (node (ref "D21") (pin "1") (pintype "passive"))
      (node (ref "R53") (pin "2") (pinfunction "2_2") (pintype "passive"))
      (node (ref "SW1") (pin "1") (pinfunction "1_1") (pintype "passive"))
      (node (ref "SW1") (pin "2") (pinfunction "2_2") (pintype "passive"))
      (node (ref "U103") (pin "3") (pinfunction "A2_3") (pintype "input"))
    )
    (net (code "26") (name "/GPIO47{slash}SPI-CLKp") (class "Default")
      (node (ref "D23") (pin "1") (pintype "passive"))
      (node (ref "R60") (pin "2") (pinfunction "2_2") (pintype "passive"))
      (node (ref "SW3") (pin "1") (pinfunction "1_1") (pintype "passive"))
      (node (ref "SW3") (pin "2") (pinfunction "2_2") (pintype "passive"))
      (node (ref "U104") (pin "1") (pinfunction "A1_1") (pintype "input"))
    )
    (net (code "27") (name "/GPIO48{slash}SPI-CLKn") (class "Default")
      (node (ref "D24") (pin "1") (pintype "passive"))
      (node (ref "R61") (pin "2") (pinfunction "2_2") (pintype "passive"))
      (node (ref "SW4") (pin "1") (pinfunction "1_1") (pintype "passive"))
      (node (ref "SW4") (pin "2") (pinfunction "2_2") (pintype "passive"))
      (node (ref "U104") (pin "3") (pinfunction "A2_3") (pintype "input"))
    )
    (net (code "28") (name "/REFIO1{slash}UART0-DTR") (class "Default")
      (node (ref "R58") (pin "1") (pinfunction "1_1") (pintype "passive"))
      (node (ref "TP53") (pin "1") (pintype "passive"))
      (node (ref "U103") (pin "13") (pinfunction "B7_13") (pintype "output"))
    )
    (net (code "29") (name "/REFIO6{slash}UART0-CTS") (class "Default")
      (node (ref "R57") (pin "1") (pinfunction "1_1") (pintype "passive"))
      (node (ref "TP52") (pin "1") (pintype "passive"))
      (node (ref "U103") (pin "14") (pinfunction "B6_14") (pintype "output"))
    )
    (net (code "30") (name "/REFIO7{slash}UART0-DSR") (class "Default")
      (node (ref "R59") (pin "1") (pinfunction "1_1") (pintype "passive"))
      (node (ref "TP54") (pin "1") (pintype "passive"))
      (node (ref "U103") (pin "12") (pinfunction "B8_12") (pintype "output"))
    )
    (net (code "31") (name "/REFIO10{slash}FSPI-IO4") (class "Default")
      (node (ref "R51") (pin "1") (pinfunction "1_1") (pintype "passive"))
      (node (ref "TP31") (pin "1") (pintype "passive"))
      (node (ref "U102") (pin "12") (pinfunction "B8_12") (pintype "output"))
    )
    (net (code "32") (name "/REFIO14{slash}FSPI-DQS") (class "Default")
      (node (ref "R52") (pin "1") (pinfunction "1_1") (pintype "passive"))
      (node (ref "TP32") (pin "1") (pintype "passive"))
      (node (ref "U103") (pin "20") (pinfunction "B1_20") (pintype "output"))
    )
    (net (code "33") (name "/REFIO17{slash}I2C-SCL") (class "Default")
      (node (ref "R64") (pin "1") (pinfunction "1_1") (pintype "passive"))
      (node (ref "TP58") (pin "1") (pintype "passive"))
      (node (ref "U104") (pin "16") (pinfunction "B4_16") (pintype "output"))
    )
    (net (code "34") (name "/REFIO18{slash}I2C-SDA") (class "Default")
      (node (ref "R63") (pin "1") (pinfunction "1_1") (pintype "passive"))
      (node (ref "TP57") (pin "1") (pintype "passive"))
      (node (ref "U104") (pin "17") (pinfunction "B3_17") (pintype "output"))
    )
    (net (code "35") (name "/REFIO21") (class "Default")
      (node (ref "R43") (pin "1") (pinfunction "1_1") (pintype "passive"))
      (node (ref "TP42") (pin "1") (pintype "passive"))
      (node (ref "U102") (pin "20") (pinfunction "B1_20") (pintype "output"))
    )
    (net (code "36") (name "/REFIO33{slash}FSPI-HD") (class "Default")
      (node (ref "R50") (pin "1") (pinfunction "1_1") (pintype "passive"))
      (node (ref "TP40") (pin "1") (pintype "passive"))
      (node (ref "U102") (pin "13") (pinfunction "B7_13") (pintype "output"))
    )
    (net (code "37") (name "/REFIO34{slash}FSPI-CS0") (class "Default")
      (node (ref "R48") (pin "1") (pinfunction "1_1") (pintype "passive"))
      (node (ref "TP48") (pin "1") (pintype "passive"))
      (node (ref "U102") (pin "15") (pinfunction "B5_15") (pintype "output"))
    )
    (net (code "38") (name "/REFIO35{slash}FSPI-D") (class "Default")
      (node (ref "R47") (pin "1") (pinfunction "1_1") (pintype "passive"))
      (node (ref "TP47") (pin "1") (pintype "passive"))
      (node (ref "U102") (pin "16") (pinfunction "B4_16") (pintype "output"))
    )
    (net (code "39") (name "/REFIO36{slash}FSPI-CLK") (class "Default")
      (node (ref "R44") (pin "1") (pinfunction "1_1") (pintype "passive"))
      (node (ref "TP45") (pin "1") (pintype "passive"))
      (node (ref "U102") (pin "18") (pinfunction "B2_18") (pintype "output"))
    )
    (net (code "40") (name "/REFIO37{slash}FSPI-Q") (class "Default")
      (node (ref "R45") (pin "1") (pinfunction "1_1") (pintype "passive"))
      (node (ref "TP46") (pin "1") (pintype "passive"))
      (node (ref "U102") (pin "17") (pinfunction "B3_17") (pintype "output"))
    )
    (net (code "41") (name "/REFIO38{slash}FSPI-WP") (class "Default")
      (node (ref "R49") (pin "1") (pinfunction "1_1") (pintype "passive"))
      (node (ref "TP49") (pin "1") (pintype "passive"))
      (node (ref "U102") (pin "14") (pinfunction "B6_14") (pintype "output"))
    )
    (net (code "42") (name "/REFIO39") (class "Default")
      (node (ref "R65") (pin "1") (pinfunction "1_1") (pintype "passive"))
      (node (ref "TP139") (pin "1") (pintype "passive"))
      (node (ref "U104") (pin "15") (pinfunction "B5_15") (pintype "output"))
    )
    (net (code "43") (name "/REFIO40") (class "Default")
      (node (ref "R66") (pin "1") (pinfunction "1_1") (pintype "passive"))
      (node (ref "TP140") (pin "1") (pintype "passive"))
      (node (ref "U104") (pin "14") (pinfunction "B6_14") (pintype "output"))
    )
    (net (code "44") (name "/REFIO41") (class "Default")
      (node (ref "R67") (pin "1") (pinfunction "1_1") (pintype "passive"))
      (node (ref "TP143") (pin "1") (pintype "passive"))
      (node (ref "U104") (pin "13") (pinfunction "B7_13") (pintype "output"))
    )
    (net (code "45") (name "/REFIO42") (class "Default")
      (node (ref "R68") (pin "1") (pinfunction "1_1") (pintype "passive"))
      (node (ref "TP144") (pin "1") (pintype "passive"))
      (node (ref "U104") (pin "12") (pinfunction "B8_12") (pintype "output"))
    )
    (net (code "46") (name "/REFIO43{slash}UART0-TxD") (class "Default")
      (node (ref "R54") (pin "1") (pinfunction "1_1") (pintype "passive"))
      (node (ref "TP37") (pin "1") (pintype "passive"))
      (node (ref "U103") (pin "17") (pinfunction "B3_17") (pintype "output"))
    )
    (net (code "47") (name "/REFIO44{slash}UART0-RxD") (class "Default")
      (node (ref "R55") (pin "1") (pinfunction "1_1") (pintype "passive"))
      (node (ref "TP38") (pin "1") (pintype "passive"))
      (node (ref "U103") (pin "16") (pinfunction "B4_16") (pintype "output"))
    )
    (net (code "48") (name "/REFIO45{slash}UART0-RTS") (class "Default")
      (node (ref "R56") (pin "1") (pinfunction "1_1") (pintype "passive"))
      (node (ref "TP51") (pin "1") (pintype "passive"))
      (node (ref "U103") (pin "15") (pinfunction "B5_15") (pintype "output"))
    )
    (net (code "49") (name "/REFIO46") (class "Default")
      (node (ref "R53") (pin "1") (pinfunction "1_1") (pintype "passive"))
      (node (ref "TP36") (pin "1") (pintype "passive"))
      (node (ref "U103") (pin "18") (pinfunction "B2_18") (pintype "output"))
    )
    (net (code "50") (name "/REFIO47{slash}SPI-CLKp") (class "Default")
      (node (ref "R60") (pin "1") (pinfunction "1_1") (pintype "passive"))
      (node (ref "TP55") (pin "1") (pintype "passive"))
      (node (ref "U104") (pin "20") (pinfunction "B1_20") (pintype "output"))
    )
    (net (code "51") (name "/REFIO48{slash}SPI-CLKn") (class "Default")
      (node (ref "R61") (pin "1") (pinfunction "1_1") (pintype "passive"))
      (node (ref "TP56") (pin "1") (pintype "passive"))
      (node (ref "U104") (pin "18") (pinfunction "B2_18") (pintype "output"))
    )
    (net (code "54") (name "GND") (class "Default")
      (node (ref "C19") (pin "2") (pinfunction "2_2") (pintype "passive"))
      (node (ref "C22") (pin "2") (pinfunction "2_2") (pintype "passive"))
      (node (ref "C23") (pin "2") (pinfunction "2_2") (pintype "passive"))
      (node (ref "C25") (pin "2") (pinfunction "2_2") (pintype "passive"))
      (node (ref "C26") (pin "2") (pinfunction "2_2") (pintype "passive"))
      (node (ref "C27") (pin "2") (pinfunction "2_2") (pintype "passive"))
      (node (ref "C29") (pin "2") (pinfunction "2_2") (pintype "passive"))
      (node (ref "C39") (pin "2") (pinfunction "2_2") (pintype "passive"))
      (node (ref "C40") (pin "2") (pinfunction "2_2") (pintype "passive"))
      (node (ref "D21") (pin "2") (pintype "passive"))
      (node (ref "D23") (pin "2") (pintype "passive"))
      (node (ref "D24") (pin "2") (pintype "passive"))
      (node (ref "SW1") (pin "3") (pinfunction "3_3") (pintype "passive"))
      (node (ref "SW1") (pin "4") (pinfunction "4_4") (pintype "passive"))
      (node (ref "SW3") (pin "3") (pinfunction "3_3") (pintype "passive"))
      (node (ref "SW3") (pin "4") (pinfunction "4_4") (pintype "passive"))
      (node (ref "SW4") (pin "3") (pinfunction "3_3") (pintype "passive"))
      (node (ref "SW4") (pin "4") (pinfunction "4_4") (pintype "passive"))
      (node (ref "U102") (pin "11") (pinfunction "GND_11") (pintype "power_in"))
      (node (ref "U103") (pin "11") (pinfunction "GND_11") (pintype "power_in"))
      (node (ref "U104") (pin "11") (pinfunction "GND_11") (pintype "power_in"))
      (node (ref "U3") (pin "2") (pinfunction "GND_2") (pintype "power_in"))
      (node (ref "U4") (pin "2") (pinfunction "GND_2") (pintype "power_in"))
      (node (ref "U7") (pin "2") (pinfunction "GND_2") (pintype "power_in"))
    )
    (net (code "55") (name "IOREF") (class "Default")
      (node (ref "C26") (pin "1") (pinfunction "1_1") (pintype "passive"))
      (node (ref "C27") (pin "1") (pinfunction "1_1") (pintype "passive"))
      (node (ref "C29") (pin "1") (pinfunction "1_1") (pintype "passive"))
      (node (ref "U102") (pin "19") (pinfunction "VCCB_19") (pintype "power_in"))
      (node (ref "U103") (pin "19") (pinfunction "VCCB_19") (pintype "power_in"))
      (node (ref "U104") (pin "19") (pinfunction "VCCB_19") (pintype "power_in"))
    )
    (net (code "56") (name "Net-(D4-C)") (class "Default")
      (node (ref "D4") (pin "1") (pinfunction "C_1") (pintype "passive"))
      (node (ref "R76") (pin "2") (pinfunction "2_2") (pintype "passive"))
    )
    (net (code "57") (name "Net-(D5-C)") (class "Default")
      (node (ref "D5") (pin "1") (pinfunction "C_1") (pintype "passive"))
      (node (ref "R93") (pin "2") (pinfunction "2_2") (pintype "passive"))
    )
    (net (code "58") (name "Net-(D6-C)") (class "Default")
      (node (ref "D6") (pin "1") (pinfunction "C_1") (pintype "passive"))
      (node (ref "R74") (pin "2") (pinfunction "2_2") (pintype "passive"))
    )
    (net (code "59") (name "Net-(D7-C)") (class "Default")
      (node (ref "D7") (pin "1") (pinfunction "C_1") (pintype "passive"))
      (node (ref "R75") (pin "2") (pinfunction "2_2") (pintype "passive"))
    )
    (net (code "60") (name "Net-(D8-C)") (class "Default")
      (node (ref "D8") (pin "1") (pinfunction "C_1") (pintype "passive"))
      (node (ref "R72") (pin "2") (pinfunction "2_2") (pintype "passive"))
    )
    (net (code "61") (name "Net-(D9-C)") (class "Default")
      (node (ref "D9") (pin "1") (pinfunction "C_1") (pintype "passive"))
      (node (ref "R73") (pin "2") (pinfunction "2_2") (pintype "passive"))
    )
    (net (code "62") (name "Net-(U3-1Y)") (class "Default")
      (node (ref "R72") (pin "1") (pinfunction "1_1") (pintype "passive"))
      (node (ref "U3") (pin "6") (pinfunction "1Y_6") (pintype "output"))
    )
    (net (code "63") (name "Net-(U3-2Y)") (class "Default")
      (node (ref "R73") (pin "1") (pinfunction "1_1") (pintype "passive"))
      (node (ref "U3") (pin "4") (pinfunction "2Y_4") (pintype "output"))
    )
    (net (code "64") (name "Net-(U4-1Y)") (class "Default")
      (node (ref "R74") (pin "1") (pinfunction "1_1") (pintype "passive"))
      (node (ref "U4") (pin "6") (pinfunction "1Y_6") (pintype "output"))
    )
    (net (code "65") (name "Net-(U4-2Y)") (class "Default")
      (node (ref "R75") (pin "1") (pinfunction "1_1") (pintype "passive"))
      (node (ref "U4") (pin "4") (pinfunction "2Y_4") (pintype "output"))
    )
    (net (code "66") (name "Net-(U7-1Y)") (class "Default")
      (node (ref "R76") (pin "1") (pinfunction "1_1") (pintype "passive"))
      (node (ref "U7") (pin "6") (pinfunction "1Y_6") (pintype "output"))
    )
    (net (code "67") (name "Net-(U7-2Y)") (class "Default")
      (node (ref "R93") (pin "1") (pinfunction "1_1") (pintype "passive"))
      (node (ref "U7") (pin "4") (pinfunction "2Y_4") (pintype "output"))
    )
  )
)
